# HydraBus_1_0_Shield_Template_Rev0.net
KiCad netlist of a schematic drawn in EAGLE
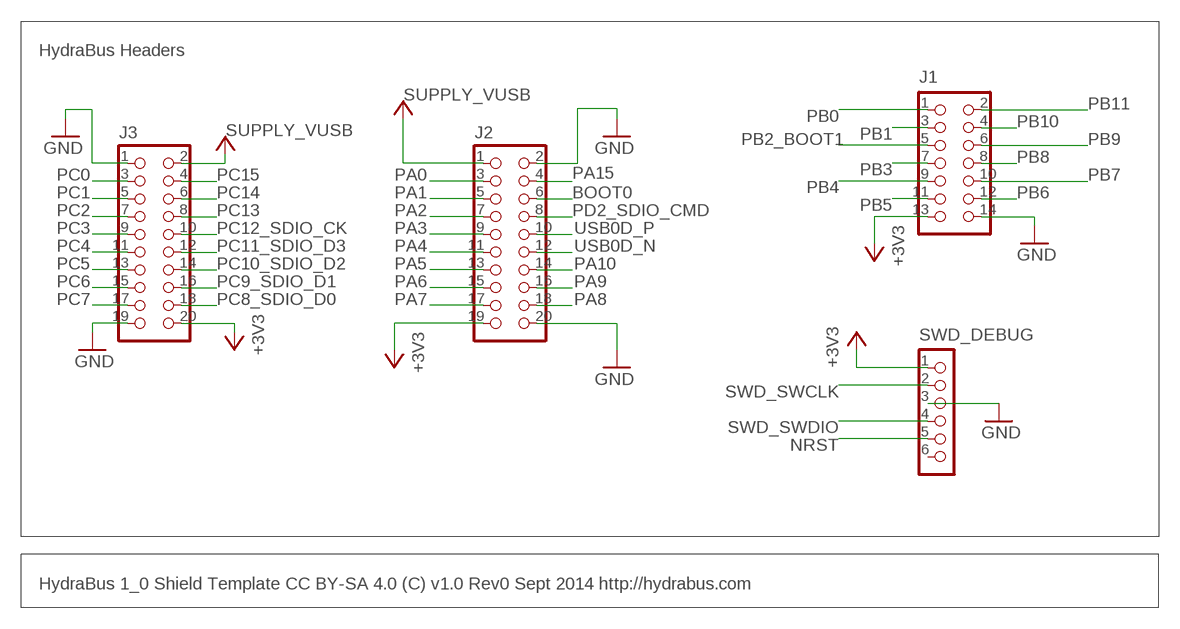
[diagram p0: schematic, sheet 1]

(export (version "E")
  (design (tool "Eeschema 10.0.6"))
  (components
    (comp (ref "J1")
      (value "HYDRABUS_SHIELD_CON_HEADER_2X07")
      (footprint "eagle-import:HYDRABUS_SHIELD_M2X7")
      (libsource (lib "eagle-import") (part "HYDRABUS_SHIELD_CON_HEADER_2X07"))
    )
    (comp (ref "J2")
      (value "HYDRABUS_SHIELD_CON_HEADER_2X10")
      (footprint "eagle-import:HYDRABUS_SHIELD_M2X10")
      (libsource (lib "eagle-import") (part "HYDRABUS_SHIELD_CON_HEADER_2X10"))
    )
    (comp (ref "J3")
      (value "HYDRABUS_SHIELD_CON_HEADER_2X10")
      (footprint "eagle-import:HYDRABUS_SHIELD_M2X10")
      (libsource (lib "eagle-import") (part "HYDRABUS_SHIELD_CON_HEADER_2X10"))
    )
    (comp (ref "SWD_DEBUG")
      (value "HYDRABUS_SHIELD_CON_HEADER_1X06")
      (footprint "eagle-import:HYDRABUS_SHIELD_M1X6")
      (libsource (lib "eagle-import") (part "HYDRABUS_SHIELD_CON_HEADER_1X06"))
    )
  )
  (nets
    (net (code "1") (name "+3V3") (class "Default")
      (node (ref "J1") (pin "13") (pinfunction "13_13") (pintype "passive"))
      (node (ref "J2") (pin "19") (pinfunction "19_19") (pintype "passive"))
      (node (ref "J3") (pin "20") (pinfunction "20_20") (pintype "passive"))
      (node (ref "SWD_DEBUG") (pin "1") (pinfunction "1_1") (pintype "bidirectional"))
    )
    (net (code "2") (name "/BOOT0") (class "Default")
      (node (ref "J2") (pin "6") (pinfunction "6_6") (pintype "passive"))
    )
    (net (code "3") (name "/NRST") (class "Default")
      (node (ref "SWD_DEBUG") (pin "5") (pinfunction "5_5") (pintype "passive"))
    )
    (net (code "4") (name "/PA0") (class "Default")
      (node (ref "J2") (pin "3") (pinfunction "3_3") (pintype "passive"))
    )
    (net (code "5") (name "/PA1") (class "Default")
      (node (ref "J2") (pin "5") (pinfunction "5_5") (pintype "passive"))
    )
    (net (code "6") (name "/PA2") (class "Default")
      (node (ref "J2") (pin "7") (pinfunction "7_7") (pintype "passive"))
    )
    (net (code "7") (name "/PA3") (class "Default")
      (node (ref "J2") (pin "9") (pinfunction "9_9") (pintype "passive"))
    )
    (net (code "8") (name "/PA4") (class "Default")
      (node (ref "J2") (pin "11") (pinfunction "11_11") (pintype "passive"))
    )
    (net (code "9") (name "/PA5") (class "Default")
      (node (ref "J2") (pin "13") (pinfunction "13_13") (pintype "passive"))
    )
    (net (code "10") (name "/PA6") (class "Default")
      (node (ref "J2") (pin "15") (pinfunction "15_15") (pintype "passive"))
    )
    (net (code "11") (name "/PA7") (class "Default")
      (node (ref "J2") (pin "17") (pinfunction "17_17") (pintype "passive"))
    )
    (net (code "12") (name "/PA8") (class "Default")
      (node (ref "J2") (pin "18") (pinfunction "18_18") (pintype "passive"))
    )
    (net (code "13") (name "/PA9") (class "Default")
      (node (ref "J2") (pin "16") (pinfunction "16_16") (pintype "passive"))
    )
    (net (code "14") (name "/PA10") (class "Default")
      (node (ref "J2") (pin "14") (pinfunction "14_14") (pintype "passive"))
    )
    (net (code "15") (name "/PA15") (class "Default")
      (node (ref "J2") (pin "4") (pinfunction "4_4") (pintype "passive"))
    )
    (net (code "16") (name "/PB0") (class "Default")
      (node (ref "J1") (pin "1") (pinfunction "1_1") (pintype "passive"))
    )
    (net (code "17") (name "/PB1") (class "Default")
      (node (ref "J1") (pin "3") (pinfunction "3_3") (pintype "passive"))
    )
    (net (code "18") (name "/PB2_BOOT1") (class "Default")
      (node (ref "J1") (pin "5") (pinfunction "5_5") (pintype "passive"))
    )
    (net (code "19") (name "/PB3") (class "Default")
      (node (ref "J1") (pin "7") (pinfunction "7_7") (pintype "passive"))
    )
    (net (code "20") (name "/PB4") (class "Default")
      (node (ref "J1") (pin "9") (pinfunction "9_9") (pintype "passive"))
    )
    (net (code "21") (name "/PB5") (class "Default")
      (node (ref "J1") (pin "11") (pinfunction "11_11") (pintype "passive"))
    )
    (net (code "22") (name "/PB6") (class "Default")
      (node (ref "J1") (pin "12") (pinfunction "12_12") (pintype "passive"))
    )
    (net (code "23") (name "/PB7") (class "Default")
      (node (ref "J1") (pin "10") (pinfunction "10_10") (pintype "passive"))
    )
    (net (code "24") (name "/PB8") (class "Default")
      (node (ref "J1") (pin "8") (pinfunction "8_8") (pintype "passive"))
    )
    (net (code "25") (name "/PB9") (class "Default")
      (node (ref "J1") (pin "6") (pinfunction "6_6") (pintype "passive"))
    )
    (net (code "26") (name "/PB10") (class "Default")
      (node (ref "J1") (pin "4") (pinfunction "4_4") (pintype "passive"))
    )
    (net (code "27") (name "/PB11") (class "Default")
      (node (ref "J1") (pin "2") (pinfunction "2_2") (pintype "passive"))
    )
    (net (code "28") (name "/PC0") (class "Default")
      (node (ref "J3") (pin "3") (pinfunction "3_3") (pintype "passive"))
    )
    (net (code "29") (name "/PC1") (class "Default")
      (node (ref "J3") (pin "5") (pinfunction "5_5") (pintype "passive"))
    )
    (net (code "30") (name "/PC2") (class "Default")
      (node (ref "J3") (pin "7") (pinfunction "7_7") (pintype "passive"))
    )
    (net (code "31") (name "/PC3") (class "Default")
      (node (ref "J3") (pin "9") (pinfunction "9_9") (pintype "passive"))
    )
    (net (code "32") (name "/PC4") (class "Default")
      (node (ref "J3") (pin "11") (pinfunction "11_11") (pintype "passive"))
    )
    (net (code "33") (name "/PC5") (class "Default")
      (node (ref "J3") (pin "13") (pinfunction "13_13") (pintype "passive"))
    )
    (net (code "34") (name "/PC6") (class "Default")
      (node (ref "J3") (pin "15") (pinfunction "15_15") (pintype "passive"))
    )
    (net (code "35") (name "/PC7") (class "Default")
      (node (ref "J3") (pin "17") (pinfunction "17_17") (pintype "passive"))
    )
    (net (code "36") (name "/PC8_SDIO_D0") (class "Default")
      (node (ref "J3") (pin "18") (pinfunction "18_18") (pintype "passive"))
    )
    (net (code "37") (name "/PC9_SDIO_D1") (class "Default")
      (node (ref "J3") (pin "16") (pinfunction "16_16") (pintype "passive"))
    )
    (net (code "38") (name "/PC10_SDIO_D2") (class "Default")
      (node (ref "J3") (pin "14") (pinfunction "14_14") (pintype "passive"))
    )
    (net (code "39") (name "/PC11_SDIO_D3") (class "Default")
      (node (ref "J3") (pin "12") (pinfunction "12_12") (pintype "passive"))
    )
    (net (code "40") (name "/PC12_SDIO_CK") (class "Default")
      (node (ref "J3") (pin "10") (pinfunction "10_10") (pintype "passive"))
    )
    (net (code "41") (name "/PC13") (class "Default")
      (node (ref "J3") (pin "8") (pinfunction "8_8") (pintype "passive"))
    )
    (net (code "42") (name "/PC14") (class "Default")
      (node (ref "J3") (pin "6") (pinfunction "6_6") (pintype "passive"))
    )
    (net (code "43") (name "/PC15") (class "Default")
      (node (ref "J3") (pin "4") (pinfunction "4_4") (pintype "passive"))
    )
    (net (code "44") (name "/PD2_SDIO_CMD") (class "Default")
      (node (ref "J2") (pin "8") (pinfunction "8_8") (pintype "passive"))
    )
    (net (code "45") (name "/SWD_SWCLK") (class "Default")
      (node (ref "SWD_DEBUG") (pin "2") (pinfunction "2_2") (pintype "bidirectional"))
    )
    (net (code "46") (name "/SWD_SWDIO") (class "Default")
      (node (ref "SWD_DEBUG") (pin "4") (pinfunction "4_4") (pintype "passive"))
    )
    (net (code "47") (name "/USB0D_N") (class "Default")
      (node (ref "J2") (pin "12") (pinfunction "12_12") (pintype "passive"))
    )
    (net (code "48") (name "/USB0D_P") (class "Default")
      (node (ref "J2") (pin "10") (pinfunction "10_10") (pintype "passive"))
    )
    (net (code "49") (name "GND") (class "Default")
      (node (ref "J1") (pin "14") (pinfunction "14_14") (pintype "passive"))
      (node (ref "J2") (pin "2") (pinfunction "2_2") (pintype "passive"))
      (node (ref "J2") (pin "20") (pinfunction "20_20") (pintype "passive"))
      (node (ref "J3") (pin "1") (pinfunction "1_1") (pintype "passive"))
      (node (ref "J3") (pin "19") (pinfunction "19_19") (pintype "passive"))
      (node (ref "SWD_DEBUG") (pin "3") (pinfunction "3_3") (pintype "passive"))
    )
    (net (code "50") (name "SUPPLY_VUSB") (class "Default")
      (node (ref "J2") (pin "1") (pinfunction "1_1") (pintype "passive"))
      (node (ref "J3") (pin "2") (pinfunction "2_2") (pintype "passive"))
    )
    (net (code "51") (name "unconnected-(SWD_DEBUG-Pad6)") (class "Default")
      (node (ref "SWD_DEBUG") (pin "6") (pinfunction "6_6") (pintype "passive"))
    )
  )
)
